# interface.net
KiCad netlist of a schematic drawn in Altium Designer
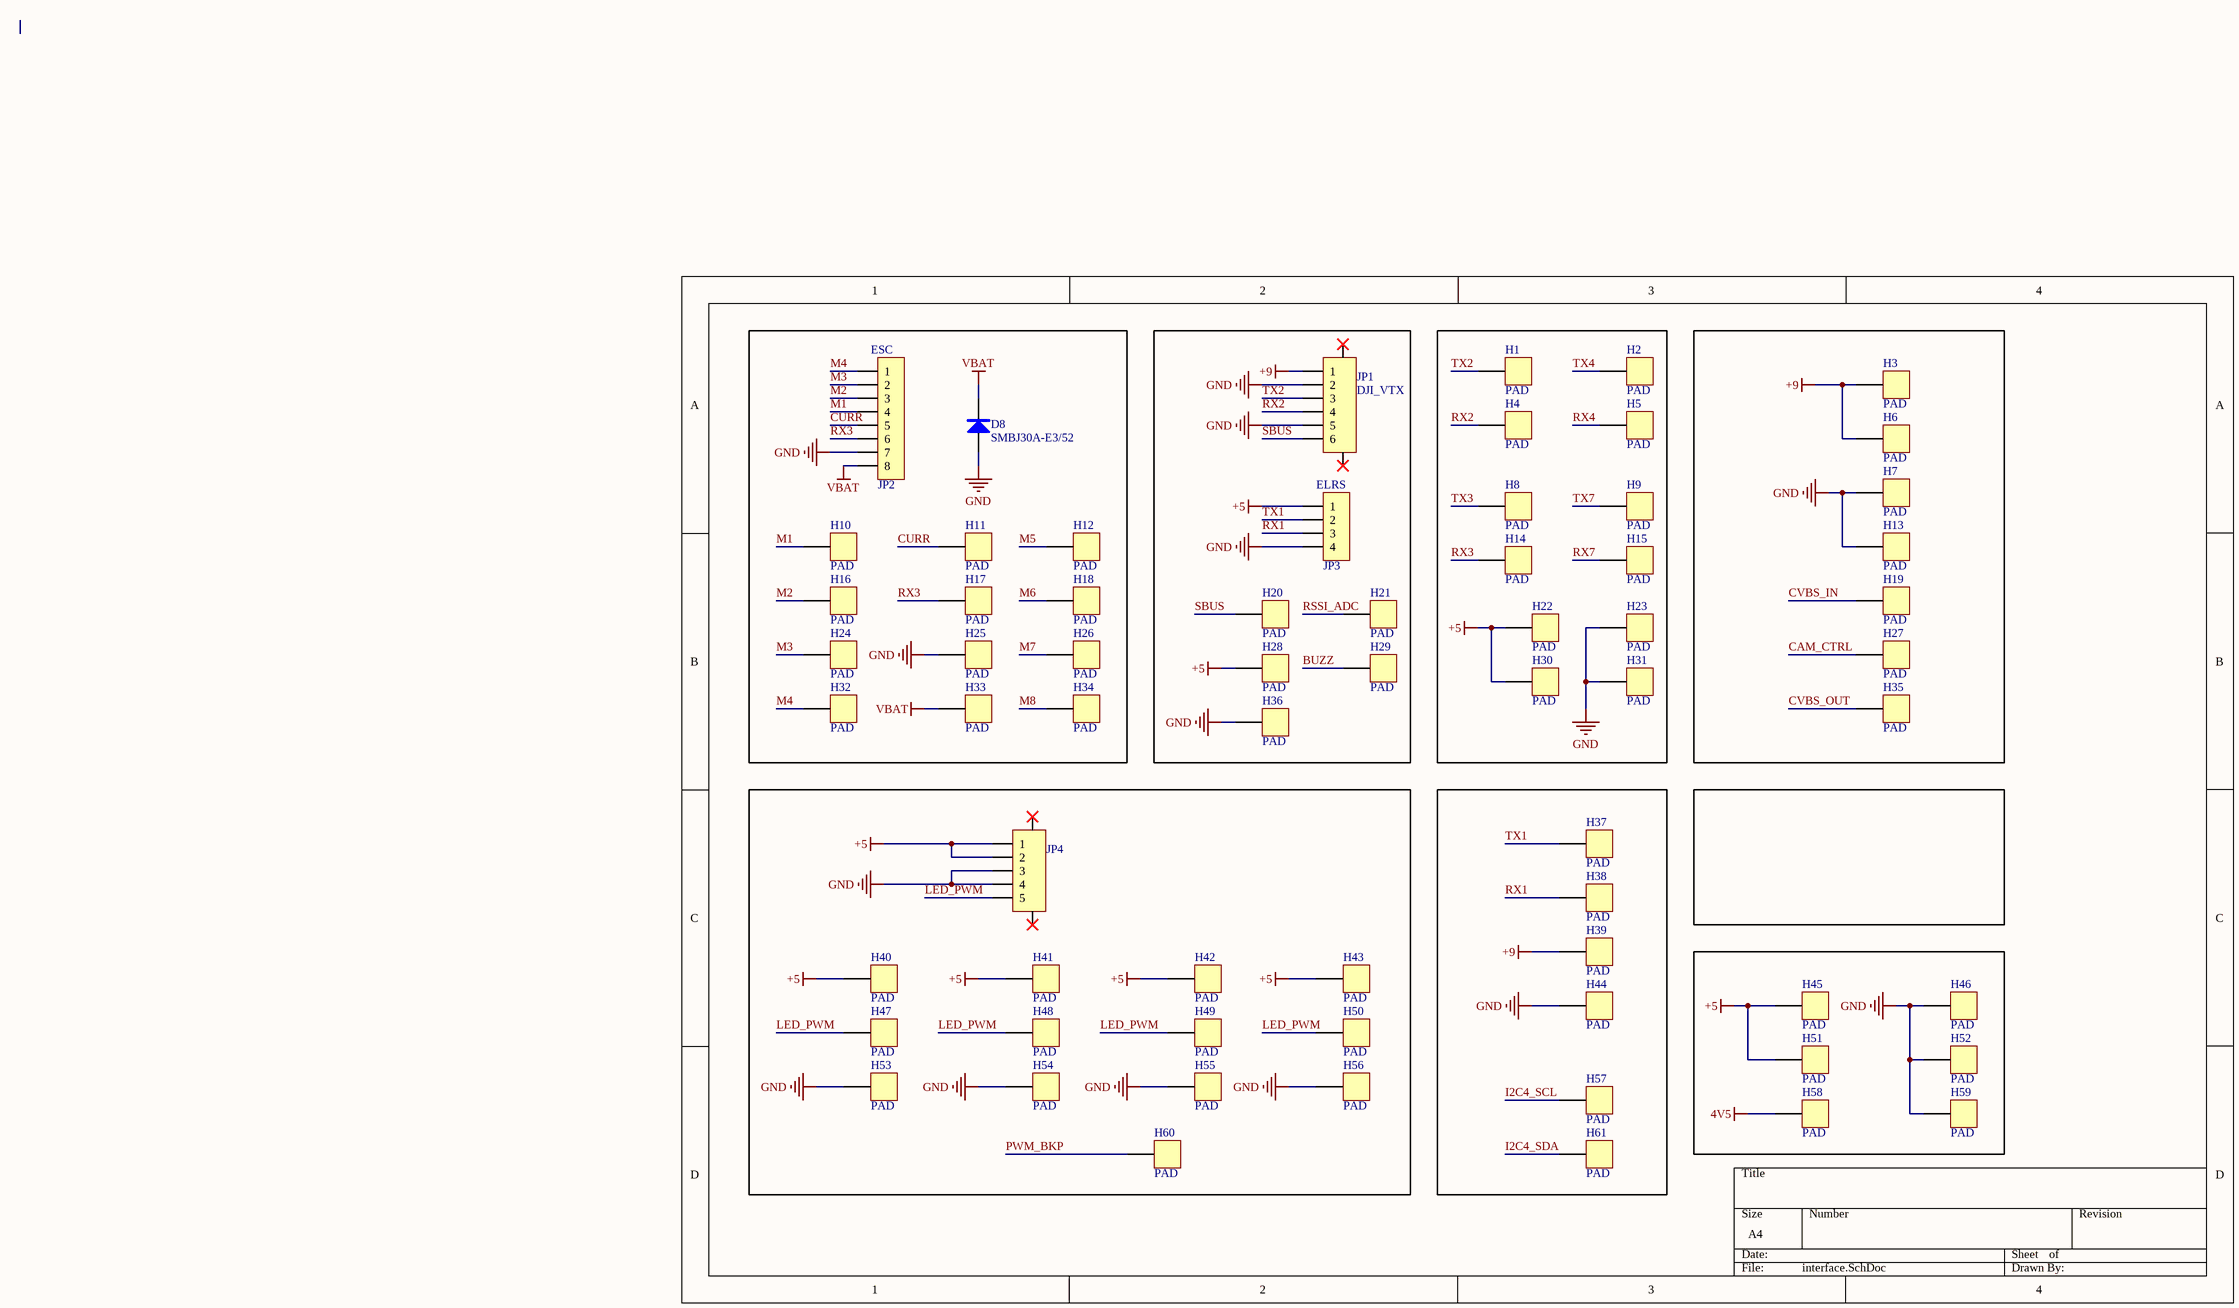
[diagram p0: interface.SchDoc]

(export (version "E")
  (design (tool "Eeschema 10.0.6"))
  (components
    (comp (ref "D8")
      (value "SMBJ30A-E3/52")
      (footprint "SMB")
      (description "30V 600W 瞬态抑制二极管(TVS)")
      (libsource (lib "AxisQuad Components Lib") (part "SMBJ30A-E3/52"))
    )
    (comp (ref "H1")
      (value "PAD")
      (footprint "Pad 4")
      (description "Pads")
      (libsource (lib "Daedalus Components Lib") (part "PAD"))
    )
    (comp (ref "H2")
      (value "PAD")
      (footprint "Pad 4")
      (description "Pads")
      (libsource (lib "Daedalus Components Lib") (part "PAD"))
    )
    (comp (ref "H3")
      (value "PAD")
      (footprint "Pad 4")
      (description "Pads")
      (libsource (lib "Daedalus Components Lib") (part "PAD"))
    )
    (comp (ref "H4")
      (value "PAD")
      (footprint "Pad 4")
      (description "Pads")
      (libsource (lib "Daedalus Components Lib") (part "PAD"))
    )
    (comp (ref "H5")
      (value "PAD")
      (footprint "Pad 4")
      (description "Pads")
      (libsource (lib "Daedalus Components Lib") (part "PAD"))
    )
    (comp (ref "H6")
      (value "PAD")
      (footprint "Pad 4")
      (description "Pads")
      (libsource (lib "Daedalus Components Lib") (part "PAD"))
    )
    (comp (ref "H7")
      (value "PAD")
      (footprint "Pad 4")
      (description "Pads")
      (libsource (lib "Daedalus Components Lib") (part "PAD"))
    )
    (comp (ref "H8")
      (value "PAD")
      (footprint "Pad 4")
      (description "Pads")
      (libsource (lib "Daedalus Components Lib") (part "PAD"))
    )
    (comp (ref "H9")
      (value "PAD")
      (footprint "Pad 4")
      (description "Pads")
      (libsource (lib "Daedalus Components Lib") (part "PAD"))
    )
    (comp (ref "H10")
      (value "PAD")
      (footprint "Pad 4")
      (description "Pads")
      (libsource (lib "Daedalus Components Lib") (part "PAD"))
    )
    (comp (ref "H11")
      (value "PAD")
      (footprint "Pad 4")
      (description "Pads")
      (libsource (lib "Daedalus Components Lib") (part "PAD"))
    )
    (comp (ref "H12")
      (value "PAD")
      (footprint "Pad 4")
      (description "Pads")
      (libsource (lib "Daedalus Components Lib") (part "PAD"))
    )
    (comp (ref "H13")
      (value "PAD")
      (footprint "Pad 4")
      (description "Pads")
      (libsource (lib "Daedalus Components Lib") (part "PAD"))
    )
    (comp (ref "H14")
      (value "PAD")
      (footprint "Pad 4")
      (description "Pads")
      (libsource (lib "Daedalus Components Lib") (part "PAD"))
    )
    (comp (ref "H15")
      (value "PAD")
      (footprint "Pad 4")
      (description "Pads")
      (libsource (lib "Daedalus Components Lib") (part "PAD"))
    )
    (comp (ref "H16")
      (value "PAD")
      (footprint "Pad 4")
      (description "Pads")
      (libsource (lib "Daedalus Components Lib") (part "PAD"))
    )
    (comp (ref "H17")
      (value "PAD")
      (footprint "Pad 4")
      (description "Pads")
      (libsource (lib "Daedalus Components Lib") (part "PAD"))
    )
    (comp (ref "H18")
      (value "PAD")
      (footprint "Pad 4")
      (description "Pads")
      (libsource (lib "Daedalus Components Lib") (part "PAD"))
    )
    (comp (ref "H19")
      (value "PAD")
      (footprint "Pad 4")
      (description "Pads")
      (libsource (lib "Daedalus Components Lib") (part "PAD"))
    )
    (comp (ref "H20")
      (value "PAD")
      (footprint "Pad 4")
      (description "Pads")
      (libsource (lib "Daedalus Components Lib") (part "PAD"))
    )
    (comp (ref "H21")
      (value "PAD")
      (footprint "Pad 4")
      (description "Pads")
      (libsource (lib "Daedalus Components Lib") (part "PAD"))
    )
    (comp (ref "H22")
      (value "PAD")
      (footprint "Pad 4")
      (description "Pads")
      (libsource (lib "Daedalus Components Lib") (part "PAD"))
    )
    (comp (ref "H23")
      (value "PAD")
      (footprint "Pad 4")
      (description "Pads")
      (libsource (lib "Daedalus Components Lib") (part "PAD"))
    )
    (comp (ref "H24")
      (value "PAD")
      (footprint "Pad 4")
      (description "Pads")
      (libsource (lib "Daedalus Components Lib") (part "PAD"))
    )
    (comp (ref "H25")
      (value "PAD")
      (footprint "Pad 4")
      (description "Pads")
      (libsource (lib "Daedalus Components Lib") (part "PAD"))
    )
    (comp (ref "H26")
      (value "PAD")
      (footprint "Pad 4")
      (description "Pads")
      (libsource (lib "Daedalus Components Lib") (part "PAD"))
    )
    (comp (ref "H27")
      (value "PAD")
      (footprint "Pad 4")
      (description "Pads")
      (libsource (lib "Daedalus Components Lib") (part "PAD"))
    )
    (comp (ref "H28")
      (value "PAD")
      (footprint "Pad 4")
      (description "Pads")
      (libsource (lib "Daedalus Components Lib") (part "PAD"))
    )
    (comp (ref "H29")
      (value "PAD")
      (footprint "Pad 4")
      (description "Pads")
      (libsource (lib "Daedalus Components Lib") (part "PAD"))
    )
    (comp (ref "H30")
      (value "PAD")
      (footprint "Pad 4")
      (description "Pads")
      (libsource (lib "Daedalus Components Lib") (part "PAD"))
    )
    (comp (ref "H31")
      (value "PAD")
      (footprint "Pad 4")
      (description "Pads")
      (libsource (lib "Daedalus Components Lib") (part "PAD"))
    )
    (comp (ref "H32")
      (value "PAD")
      (footprint "Pad 4")
      (description "Pads")
      (libsource (lib "Daedalus Components Lib") (part "PAD"))
    )
    (comp (ref "H33")
      (value "PAD")
      (footprint "Pad 4")
      (description "Pads")
      (libsource (lib "Daedalus Components Lib") (part "PAD"))
    )
    (comp (ref "H34")
      (value "PAD")
      (footprint "Pad 4")
      (description "Pads")
      (libsource (lib "Daedalus Components Lib") (part "PAD"))
    )
    (comp (ref "H35")
      (value "PAD")
      (footprint "Pad 4")
      (description "Pads")
      (libsource (lib "Daedalus Components Lib") (part "PAD"))
    )
    (comp (ref "H36")
      (value "PAD")
      (footprint "Pad 4")
      (description "Pads")
      (libsource (lib "Daedalus Components Lib") (part "PAD"))
    )
    (comp (ref "H37")
      (value "PAD")
      (footprint "Pad 4")
      (description "Pads")
      (libsource (lib "Daedalus Components Lib") (part "PAD"))
    )
    (comp (ref "H38")
      (value "PAD")
      (footprint "Pad 4")
      (description "Pads")
      (libsource (lib "Daedalus Components Lib") (part "PAD"))
    )
    (comp (ref "H39")
      (value "PAD")
      (footprint "Pad 4")
      (description "Pads")
      (libsource (lib "Daedalus Components Lib") (part "PAD"))
    )
    (comp (ref "H40")
      (value "PAD")
      (footprint "Pad 2")
      (description "Pads")
      (libsource (lib "Daedalus Components Lib") (part "PAD"))
    )
    (comp (ref "H41")
      (value "PAD")
      (footprint "Pad 2")
      (description "Pads")
      (libsource (lib "Daedalus Components Lib") (part "PAD"))
    )
    (comp (ref "H42")
      (value "PAD")
      (footprint "Pad 2")
      (description "Pads")
      (libsource (lib "Daedalus Components Lib") (part "PAD"))
    )
    (comp (ref "H43")
      (value "PAD")
      (footprint "Pad 2")
      (description "Pads")
      (libsource (lib "Daedalus Components Lib") (part "PAD"))
    )
    (comp (ref "H44")
      (value "PAD")
      (footprint "Pad 4")
      (description "Pads")
      (libsource (lib "Daedalus Components Lib") (part "PAD"))
    )
    (comp (ref "H45")
      (value "PAD")
      (footprint "Pad 4")
      (description "Pads")
      (libsource (lib "Daedalus Components Lib") (part "PAD"))
    )
    (comp (ref "H46")
      (value "PAD")
      (footprint "Pad 4")
      (description "Pads")
      (libsource (lib "Daedalus Components Lib") (part "PAD"))
    )
    (comp (ref "H47")
      (value "PAD")
      (footprint "Pad 2")
      (description "Pads")
      (libsource (lib "Daedalus Components Lib") (part "PAD"))
    )
    (comp (ref "H48")
      (value "PAD")
      (footprint "Pad 2")
      (description "Pads")
      (libsource (lib "Daedalus Components Lib") (part "PAD"))
    )
    (comp (ref "H49")
      (value "PAD")
      (footprint "Pad 2")
      (description "Pads")
      (libsource (lib "Daedalus Components Lib") (part "PAD"))
    )
    (comp (ref "H50")
      (value "PAD")
      (footprint "Pad 2")
      (description "Pads")
      (libsource (lib "Daedalus Components Lib") (part "PAD"))
    )
    (comp (ref "H51")
      (value "PAD")
      (footprint "Pad 4")
      (description "Pads")
      (libsource (lib "Daedalus Components Lib") (part "PAD"))
    )
    (comp (ref "H52")
      (value "PAD")
      (footprint "Pad 4")
      (description "Pads")
      (libsource (lib "Daedalus Components Lib") (part "PAD"))
    )
    (comp (ref "H53")
      (value "PAD")
      (footprint "Pad 2")
      (description "Pads")
      (libsource (lib "Daedalus Components Lib") (part "PAD"))
    )
    (comp (ref "H54")
      (value "PAD")
      (footprint "Pad 2")
      (description "Pads")
      (libsource (lib "Daedalus Components Lib") (part "PAD"))
    )
    (comp (ref "H55")
      (value "PAD")
      (footprint "Pad 2")
      (description "Pads")
      (libsource (lib "Daedalus Components Lib") (part "PAD"))
    )
    (comp (ref "H56")
      (value "PAD")
      (footprint "Pad 2")
      (description "Pads")
      (libsource (lib "Daedalus Components Lib") (part "PAD"))
    )
    (comp (ref "H57")
      (value "PAD")
      (footprint "Pad 4")
      (description "Pads")
      (libsource (lib "Daedalus Components Lib") (part "PAD"))
    )
    (comp (ref "H58")
      (value "PAD")
      (footprint "Pad 2")
      (description "Pads")
      (libsource (lib "Daedalus Components Lib") (part "PAD"))
    )
    (comp (ref "H59")
      (value "PAD")
      (footprint "Pad 2")
      (description "Pads")
      (libsource (lib "Daedalus Components Lib") (part "PAD"))
    )
    (comp (ref "H60")
      (value "PAD")
      (footprint "Pad 2")
      (description "Pads")
      (libsource (lib "Daedalus Components Lib") (part "PAD"))
    )
    (comp (ref "H61")
      (value "PAD")
      (footprint "Pad 4")
      (description "Pads")
      (libsource (lib "Daedalus Components Lib") (part "PAD"))
    )
    (comp (ref "JP1")
      (value "CON-6P")
      (footprint "SH1.0-WT-6P")
      (description "6P连接器")
      (libsource (lib "AxisQuad Components Lib") (part "Header 6"))
    )
    (comp (ref "JP2")
      (value "CON-8P")
      (footprint "SH1.0-WT-8P")
      (description "8P连接器")
      (libsource (lib "AxisQuad Components Lib") (part "Header 8"))
    )
    (comp (ref "JP3")
      (value "CON-4P")
      (footprint "SH1.0-WT-4P")
      (description "4P连接器")
      (libsource (lib "AxisQuad Components Lib") (part "Header 4"))
    )
    (comp (ref "JP4")
      (value "CON-5P")
      (footprint "SH1.0-WT-5P")
      (description "5P连接器")
      (libsource (lib "AxisQuad Components Lib") (part "Header 5"))
    )
  )
  (nets
    (net (code "1") (name "+5") (class "Default")
      (node (ref "H22") (pin "1") (pinfunction "1_1") (pintype "passive"))
      (node (ref "H28") (pin "1") (pinfunction "1_1") (pintype "passive"))
      (node (ref "H30") (pin "1") (pinfunction "1_1") (pintype "passive"))
      (node (ref "H40") (pin "1") (pinfunction "1_1") (pintype "passive"))
      (node (ref "H41") (pin "1") (pinfunction "1_1") (pintype "passive"))
      (node (ref "H42") (pin "1") (pinfunction "1_1") (pintype "passive"))
      (node (ref "H43") (pin "1") (pinfunction "1_1") (pintype "passive"))
      (node (ref "H45") (pin "1") (pinfunction "1_1") (pintype "passive"))
      (node (ref "H51") (pin "1") (pinfunction "1_1") (pintype "passive"))
      (node (ref "JP3") (pin "1") (pinfunction "1_1") (pintype "passive"))
      (node (ref "JP4") (pin "1") (pinfunction "1_1") (pintype "passive"))
      (node (ref "JP4") (pin "2") (pinfunction "2_2") (pintype "passive"))
    )
    (net (code "2") (name "+9") (class "Default")
      (node (ref "H3") (pin "1") (pinfunction "1_1") (pintype "passive"))
      (node (ref "H39") (pin "1") (pinfunction "1_1") (pintype "passive"))
      (node (ref "H6") (pin "1") (pinfunction "1_1") (pintype "passive"))
      (node (ref "JP1") (pin "1") (pinfunction "1_1") (pintype "passive"))
    )
    (net (code "3") (name "/BUZZ") (class "Default")
      (node (ref "H29") (pin "1") (pinfunction "1_1") (pintype "passive"))
    )
    (net (code "4") (name "/CAM_CTRL") (class "Default")
      (node (ref "H27") (pin "1") (pinfunction "1_1") (pintype "passive"))
    )
    (net (code "5") (name "/CURR") (class "Default")
      (node (ref "H11") (pin "1") (pinfunction "1_1") (pintype "passive"))
      (node (ref "JP2") (pin "5") (pinfunction "5_5") (pintype "passive"))
    )
    (net (code "6") (name "/CVBS_IN") (class "Default")
      (node (ref "H19") (pin "1") (pinfunction "1_1") (pintype "passive"))
    )
    (net (code "7") (name "/CVBS_OUT") (class "Default")
      (node (ref "H35") (pin "1") (pinfunction "1_1") (pintype "passive"))
    )
    (net (code "8") (name "/I2C4_SCL") (class "Default")
      (node (ref "H57") (pin "1") (pinfunction "1_1") (pintype "passive"))
    )
    (net (code "9") (name "/I2C4_SDA") (class "Default")
      (node (ref "H61") (pin "1") (pinfunction "1_1") (pintype "passive"))
    )
    (net (code "10") (name "/LED_PWM") (class "Default")
      (node (ref "H47") (pin "1") (pinfunction "1_1") (pintype "passive"))
      (node (ref "H48") (pin "1") (pinfunction "1_1") (pintype "passive"))
      (node (ref "H49") (pin "1") (pinfunction "1_1") (pintype "passive"))
      (node (ref "H50") (pin "1") (pinfunction "1_1") (pintype "passive"))
      (node (ref "JP4") (pin "5") (pinfunction "5_5") (pintype "passive"))
    )
    (net (code "11") (name "/M1") (class "Default")
      (node (ref "H10") (pin "1") (pinfunction "1_1") (pintype "passive"))
      (node (ref "JP2") (pin "4") (pinfunction "4_4") (pintype "passive"))
    )
    (net (code "12") (name "/M2") (class "Default")
      (node (ref "H16") (pin "1") (pinfunction "1_1") (pintype "passive"))
      (node (ref "JP2") (pin "3") (pinfunction "3_3") (pintype "passive"))
    )
    (net (code "13") (name "/M3") (class "Default")
      (node (ref "H24") (pin "1") (pinfunction "1_1") (pintype "passive"))
      (node (ref "JP2") (pin "2") (pinfunction "2_2") (pintype "passive"))
    )
    (net (code "14") (name "/M4") (class "Default")
      (node (ref "H32") (pin "1") (pinfunction "1_1") (pintype "passive"))
      (node (ref "JP2") (pin "1") (pinfunction "1_1") (pintype "passive"))
    )
    (net (code "15") (name "/M5") (class "Default")
      (node (ref "H12") (pin "1") (pinfunction "1_1") (pintype "passive"))
    )
    (net (code "16") (name "/M6") (class "Default")
      (node (ref "H18") (pin "1") (pinfunction "1_1") (pintype "passive"))
    )
    (net (code "17") (name "/M7") (class "Default")
      (node (ref "H26") (pin "1") (pinfunction "1_1") (pintype "passive"))
    )
    (net (code "18") (name "/M8") (class "Default")
      (node (ref "H34") (pin "1") (pinfunction "1_1") (pintype "passive"))
    )
    (net (code "19") (name "/PWM_BKP") (class "Default")
      (node (ref "H60") (pin "1") (pinfunction "1_1") (pintype "passive"))
    )
    (net (code "20") (name "/RSSI_ADC") (class "Default")
      (node (ref "H21") (pin "1") (pinfunction "1_1") (pintype "passive"))
    )
    (net (code "21") (name "/RX1") (class "Default")
      (node (ref "H38") (pin "1") (pinfunction "1_1") (pintype "passive"))
      (node (ref "JP3") (pin "3") (pinfunction "3_3") (pintype "passive"))
    )
    (net (code "22") (name "/RX2") (class "Default")
      (node (ref "H4") (pin "1") (pinfunction "1_1") (pintype "passive"))
      (node (ref "JP1") (pin "4") (pinfunction "4_4") (pintype "passive"))
    )
    (net (code "23") (name "/RX3") (class "Default")
      (node (ref "H14") (pin "1") (pinfunction "1_1") (pintype "passive"))
      (node (ref "H17") (pin "1") (pinfunction "1_1") (pintype "passive"))
      (node (ref "JP2") (pin "6") (pinfunction "6_6") (pintype "passive"))
    )
    (net (code "24") (name "/RX4") (class "Default")
      (node (ref "H5") (pin "1") (pinfunction "1_1") (pintype "passive"))
    )
    (net (code "25") (name "/RX7") (class "Default")
      (node (ref "H15") (pin "1") (pinfunction "1_1") (pintype "passive"))
    )
    (net (code "26") (name "/SBUS") (class "Default")
      (node (ref "H20") (pin "1") (pinfunction "1_1") (pintype "passive"))
      (node (ref "JP1") (pin "6") (pinfunction "6_6") (pintype "passive"))
    )
    (net (code "27") (name "/TX1") (class "Default")
      (node (ref "H37") (pin "1") (pinfunction "1_1") (pintype "passive"))
      (node (ref "JP3") (pin "2") (pinfunction "2_2") (pintype "passive"))
    )
    (net (code "28") (name "/TX2") (class "Default")
      (node (ref "H1") (pin "1") (pinfunction "1_1") (pintype "passive"))
      (node (ref "JP1") (pin "3") (pinfunction "3_3") (pintype "passive"))
    )
    (net (code "29") (name "/TX3") (class "Default")
      (node (ref "H8") (pin "1") (pinfunction "1_1") (pintype "passive"))
    )
    (net (code "30") (name "/TX4") (class "Default")
      (node (ref "H2") (pin "1") (pinfunction "1_1") (pintype "passive"))
    )
    (net (code "31") (name "/TX7") (class "Default")
      (node (ref "H9") (pin "1") (pinfunction "1_1") (pintype "passive"))
    )
    (net (code "32") (name "4V5") (class "Default")
      (node (ref "H58") (pin "1") (pinfunction "1_1") (pintype "passive"))
    )
    (net (code "33") (name "GND") (class "Default")
      (node (ref "D8") (pin "1") (pinfunction "A_1") (pintype "passive"))
      (node (ref "H13") (pin "1") (pinfunction "1_1") (pintype "passive"))
      (node (ref "H23") (pin "1") (pinfunction "1_1") (pintype "passive"))
      (node (ref "H25") (pin "1") (pinfunction "1_1") (pintype "passive"))
      (node (ref "H31") (pin "1") (pinfunction "1_1") (pintype "passive"))
      (node (ref "H36") (pin "1") (pinfunction "1_1") (pintype "passive"))
      (node (ref "H44") (pin "1") (pinfunction "1_1") (pintype "passive"))
      (node (ref "H46") (pin "1") (pinfunction "1_1") (pintype "passive"))
      (node (ref "H52") (pin "1") (pinfunction "1_1") (pintype "passive"))
      (node (ref "H53") (pin "1") (pinfunction "1_1") (pintype "passive"))
      (node (ref "H54") (pin "1") (pinfunction "1_1") (pintype "passive"))
      (node (ref "H55") (pin "1") (pinfunction "1_1") (pintype "passive"))
      (node (ref "H56") (pin "1") (pinfunction "1_1") (pintype "passive"))
      (node (ref "H59") (pin "1") (pinfunction "1_1") (pintype "passive"))
      (node (ref "H7") (pin "1") (pinfunction "1_1") (pintype "passive"))
      (node (ref "JP1") (pin "2") (pinfunction "2_2") (pintype "passive"))
      (node (ref "JP1") (pin "5") (pinfunction "5_5") (pintype "passive"))
      (node (ref "JP2") (pin "7") (pinfunction "7_7") (pintype "passive"))
      (node (ref "JP3") (pin "4") (pinfunction "4_4") (pintype "passive"))
      (node (ref "JP4") (pin "3") (pinfunction "3_3") (pintype "passive"))
      (node (ref "JP4") (pin "4") (pinfunction "4_4") (pintype "passive"))
    )
    (net (code "34") (name "VBAT") (class "Default")
      (node (ref "D8") (pin "2") (pinfunction "K_2") (pintype "passive"))
      (node (ref "H33") (pin "1") (pinfunction "1_1") (pintype "passive"))
      (node (ref "JP2") (pin "8") (pinfunction "8_8") (pintype "passive"))
    )
    (net (code "35") (name "unconnected-(JP1-Pad0)") (class "Default")
      (node (ref "JP1") (pin "0") (pinfunction "0_0") (pintype "passive+no_connect"))
    )
    (net (code "36") (name "unconnected-(JP1-Pad0)_1") (class "Default")
      (node (ref "JP1") (pin "0") (pinfunction "0_0") (pintype "passive+no_connect"))
    )
    (net (code "37") (name "unconnected-(JP4-Pad0)") (class "Default")
      (node (ref "JP4") (pin "0") (pinfunction "0_0") (pintype "passive+no_connect"))
    )
    (net (code "38") (name "unconnected-(JP4-Pad0)_1") (class "Default")
      (node (ref "JP4") (pin "0") (pinfunction "0_0") (pintype "passive+no_connect"))
    )
  )
)
